# 3_3V_Converter.net
KiCad netlist of a schematic drawn in Altium Designer
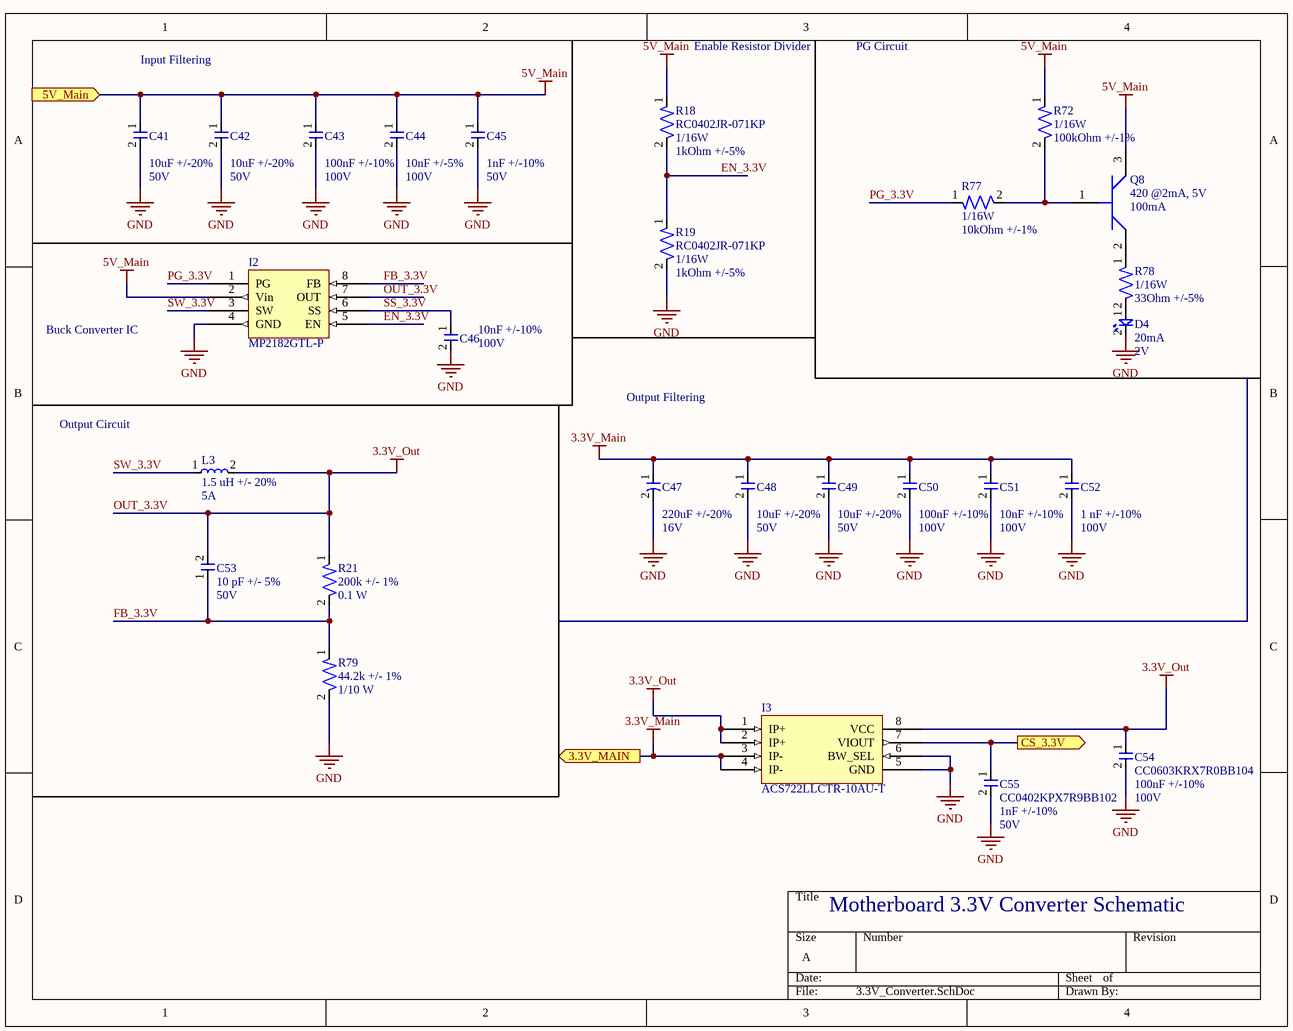
[diagram p0: 3.3V_Converter.SchDoc]

(export (version "E")
  (design (tool "Eeschema 10.0.6"))
  (components
    (comp (ref "C41")
      (value "CL31B106KBHNNNE")
      (footprint "CAP-1206")
      (description "10 µF ±10% 50V Ceramic Capacitor X7R 1206 (3216 Metric)")
      (fields
        (field (name "MANUFACTURER") "Samsung Electro-Mechanics")
        (field (name "CAPACITANCE") "10uF +/-20%")
        (field (name "VOLTAGE RATING") "50V")
      )
      (libsource (lib "MasterLib") (part "CAP-10U-0001"))
    )
    (comp (ref "C42")
      (value "CL31B106KBHNNNE")
      (footprint "CAP-1206")
      (description "10 µF ±10% 50V Ceramic Capacitor X7R 1206 (3216 Metric)")
      (fields
        (field (name "MANUFACTURER") "Samsung Electro-Mechanics")
        (field (name "CAPACITANCE") "10uF +/-20%")
        (field (name "VOLTAGE RATING") "50V")
      )
      (libsource (lib "MasterLib") (part "CAP-10U-0001"))
    )
    (comp (ref "C43")
      (value "CC0603KRX7R0BB104")
      (footprint "CAP-0603")
      (description "CAP CER 0.1UF 100V X7R 0603")
      (fields
        (field (name "MANUFACTURER") "YAGEO")
        (field (name "CAPACITANCE") "100nF +/-10%")
        (field (name "VOLTAGE RATING") "100V")
      )
      (libsource (lib "MasterLib") (part "CAP-100N-0001"))
    )
    (comp (ref "C44")
      (value "C1608C0G2A103J080AC")
      (footprint "CAP-0603")
      (description "CAP CER 10000PF 100V C0G 0603")
      (fields
        (field (name "MANUFACTURER") "TDK Corporation")
        (field (name "CAPACITANCE") "10nF +/-5%")
        (field (name "VOLTAGE RATING") "100V")
      )
      (libsource (lib "MasterLib") (part "CAP-10N-0002"))
    )
    (comp (ref "C45")
      (value "CC0402KPX7R9BB102")
      (footprint "CAP-0402")
      (description "1000 pF ±10% 50V Ceramic Capacitor X7R 0402 (1005 Metric)")
      (fields
        (field (name "MANUFACTURER") "YAGEO")
        (field (name "CAPACITANCE") "1nF +/-10%")
        (field (name "VOLTAGE RATING") "50V")
      )
      (libsource (lib "MasterLib") (part "CAP-1N-0002"))
    )
    (comp (ref "C46")
      (value "CC0402KRX7R0BB103")
      (footprint "CAP-0402")
      (description "10000 pF ±10% 100V Ceramic Capacitor X7R 0402 (1005 Metric)")
      (fields
        (field (name "MANUFACTURER") "YAGEO")
        (field (name "CAPACITANCE") "10nF +/-10%")
        (field (name "VOLTAGE RATING") "100V")
      )
      (libsource (lib "MasterLib") (part "CAP-10N-0001"))
    )
    (comp (ref "C47")
      (value "UUD1C221MCL1GS")
      (footprint "ELEC-220U-0001")
      (description "220 µF 16 V Aluminum Electrolytic Capacitors Radial, Can - SMD 2000 Hrs @ 105°C")
      (fields
        (field (name "MANUFACTURER") "Nichicon")
        (field (name "CAPACITANCE") "220uF +/-20%")
        (field (name "VOLTAGE RATING") "16V")
      )
      (libsource (lib "MasterLib") (part "ELEC-220U-0001"))
    )
    (comp (ref "C48")
      (value "CL31B106KBHNNNE")
      (footprint "CAP-1206")
      (description "10 µF ±10% 50V Ceramic Capacitor X7R 1206 (3216 Metric)")
      (fields
        (field (name "MANUFACTURER") "Samsung Electro-Mechanics")
        (field (name "CAPACITANCE") "10uF +/-20%")
        (field (name "VOLTAGE RATING") "50V")
      )
      (libsource (lib "MasterLib") (part "CAP-10U-0001"))
    )
    (comp (ref "C49")
      (value "CL31B106KBHNNNE")
      (footprint "CAP-1206")
      (description "10 µF ±10% 50V Ceramic Capacitor X7R 1206 (3216 Metric)")
      (fields
        (field (name "MANUFACTURER") "Samsung Electro-Mechanics")
        (field (name "CAPACITANCE") "10uF +/-20%")
        (field (name "VOLTAGE RATING") "50V")
      )
      (libsource (lib "MasterLib") (part "CAP-10U-0001"))
    )
    (comp (ref "C50")
      (value "CC0603KRX7R0BB104")
      (footprint "CAP-0603")
      (description "CAP CER 0.1UF 100V X7R 0603")
      (fields
        (field (name "MANUFACTURER") "YAGEO")
        (field (name "CAPACITANCE") "100nF +/-10%")
        (field (name "VOLTAGE RATING") "100V")
      )
      (libsource (lib "MasterLib") (part "CAP-100N-0001"))
    )
    (comp (ref "C51")
      (value "CC0402KRX7R0BB103")
      (footprint "CAP-0402")
      (description "10000 pF ±10% 100V Ceramic Capacitor X7R 0402 (1005 Metric)")
      (fields
        (field (name "MANUFACTURER") "YAGEO")
        (field (name "CAPACITANCE") "10nF +/-10%")
        (field (name "VOLTAGE RATING") "100V")
      )
      (libsource (lib "MasterLib") (part "CAP-10N-0001"))
    )
    (comp (ref "C52")
      (value "CAP-1N-0001")
      (footprint "CAP-0603")
      (description "1000 pF ±10% 100V Ceramic Capacitor X7R 0603 (1608 Metric)")
      (fields (field (name "CAPACITANCE") "1 nF +/-10%") (field (name "VOLTAGE") "100V"))
      (libsource (lib "MasterLib") (part "CAP-1N-0001"))
    )
    (comp (ref "C53")
      (value "0603N100J500CT")
      (footprint "CAP-0603")
      (description "10 pF ±5% 50V Ceramic Capacitor C0G, NP0 0603 (1608 Metric)")
      (fields
        (field (name "MANUFACTURER") "Walshin Technology Corporation")
        (field (name "CAPACITANCE") "10 pF +/- 5%")
        (field (name "VOLTAGE RATING") "50V")
      )
      (libsource (lib "MasterLib") (part "CAP-10P-0001"))
    )
    (comp (ref "C54")
      (value "CC0603KRX7R0BB104")
      (footprint "CAP-0603")
      (description "CAP CER 0.1UF 100V X7R 0603")
      (fields
        (field (name "MANUFACTURER") "YAGEO")
        (field (name "CAPACITANCE") "100nF +/-10%")
        (field (name "VOLTAGE RATING") "100V")
      )
      (libsource (lib "MasterLib") (part "CAP-100N-0001"))
    )
    (comp (ref "C55")
      (value "CC0402KPX7R9BB102")
      (footprint "CAP-0402")
      (description "1000 pF ±10% 50V Ceramic Capacitor X7R 0402 (1005 Metric)")
      (fields
        (field (name "MANUFACTURER") "YAGEO")
        (field (name "CAPACITANCE") "1nF +/-10%")
        (field (name "VOLTAGE RATING") "50V")
      )
      (libsource (lib "MasterLib") (part "CAP-1N-0002"))
    )
    (comp (ref "D4")
      (value "150060AS75000")
      (footprint "LED-0603")
      (description "CAP CER 0.1UF 100V X7R 0603")
      (fields
        (field (name "MANUFACTURER") "Wurth Electronik")
        (field (name "CURRENT RATING") "20mA")
        (field (name "VF") "2V")
      )
      (libsource (lib "MasterLib") (part "LED_Amber_0001"))
    )
    (comp (ref "I2")
      (value "MP2182GTL-P")
      (footprint "IC-SOT583")
      (description "Buck Switching Regulator IC Positive Adjustable 0.6V 1 Output 2A SOT-583")
      (fields (field (name "MANUFACTURER") "Monolithic Power Systems"))
      (libsource (lib "MasterLib") (part "IC-BUCK-0003"))
    )
    (comp (ref "I3")
      (value "ACS722LLCTR-10AU-T")
      (footprint "IC-CURRENT-0001")
      (description "Current Sensor 10A 1 Channel Hall Effect, Open Loop Unidirectional 8-SOIC (0.154\", 3.90mm Width)")
      (libsource (lib "MasterLib") (part "IC-CURRENT-0001"))
    )
    (comp (ref "L3")
      (value "SRP3212-1R5M")
      (footprint "IND-1210")
      (description "1.5 µH Shielded Drum Core, Wirewound Inductor 4.4 A 53mOhm Max 1210 (3225 Metric)")
      (fields
        (field (name "MANUFACTURER") "Bourns Inc.")
        (field (name "INDUCTANCE") "1.5 uH +/- 20%")
        (field (name "SATURATION CURRENT") "5A")
      )
      (libsource (lib "MasterLib") (part "PWRIND-1.5U-0001"))
    )
    (comp (ref "Q8")
      (value "BC847C,235")
      (footprint "NPN-420-0001")
      (description "Bipolar (BJT) Transistor NPN 45 V 100 mA 100MHz 250 mW Surface Mount TO-236AB")
      (fields (field (name "HFE") "420 @2mA, 5V") (field (name "IC") "100mA"))
      (libsource (lib "MasterLib") (part "BJT-420-0001"))
    )
    (comp (ref "R18")
      (value "RC0402JR-071KP")
      (footprint "RES-0402")
      (description "RES SMD 1K OHM 5% 1/16W 0402")
      (fields
        (field (name "MANUFACTURER") "YAGEO")
        (field (name "POWER RATING") "1/16W")
        (field (name "RESISTANCE") "1kOhm +/-5%")
      )
      (libsource (lib "MasterLib") (part "RES-1K-0001"))
    )
    (comp (ref "R19")
      (value "RC0402JR-071KP")
      (footprint "RES-0402")
      (description "RES SMD 1K OHM 5% 1/16W 0402")
      (fields
        (field (name "MANUFACTURER") "YAGEO")
        (field (name "POWER RATING") "1/16W")
        (field (name "RESISTANCE") "1kOhm +/-5%")
      )
      (libsource (lib "MasterLib") (part "RES-1K-0001"))
    )
    (comp (ref "R21")
      (value "ERJ-3EKF2003V")
      (footprint "RES-0603")
      (description "200 kOhms ±1% 0.1W, 1/10W Chip Resistor 0603 (1608 Metric) Automotive AEC-Q200 Thick Film")
      (fields
        (field (name "MANUFACTURER") "Panasonic Electronic Components")
        (field (name "RESISTANCE") "200k +/- 1%")
        (field (name "POWER RATING") "0.1 W")
      )
      (libsource (lib "MasterLib") (part "RES-200K-0001"))
    )
    (comp (ref "R72")
      (value "AF0402FR-07100KL")
      (footprint "RES-0402")
      (fields
        (field (name "MANUFACTURER") "YAGEO")
        (field (name "POWER RATING") "1/16W")
        (field (name "RESISTANCE") "100kOhm +/-1%")
      )
      (libsource (lib "MasterLib") (part "RES-100K-0001"))
    )
    (comp (ref "R77")
      (value "RC0402FR-0710KL")
      (footprint "RES-0402")
      (description "RES 10K OHM 1% 1/16W 0402")
      (fields
        (field (name "MANUFACTURER") "YAGEO")
        (field (name "POWER RATING") "1/16W")
        (field (name "RESISTANCE") "10kOhm +/-1%")
      )
      (libsource (lib "MasterLib") (part "RES-10K-0001"))
    )
    (comp (ref "R78")
      (value "RC0402JR-0733RP")
      (footprint "RES-0402")
      (description "RES SMD 33 OHM 5% 1/16W 0402")
      (fields
        (field (name "MANUFACTURER") "YAGEO")
        (field (name "POWER RATING") "1/16W")
        (field (name "RESISTANCE") "33Ohm +/-5%")
      )
      (libsource (lib "MasterLib") (part "RES-33-0001"))
    )
    (comp (ref "R79")
      (value "RMCF0603FT44K2")
      (footprint "RES-0603")
      (description "44.2 kOhms ±1% 0.1W, 1/10W Chip Resistor 0603 (1608 Metric) Automotive AEC-Q200 Thick Film")
      (fields (field (name "RESISTANCE") "44.2k +/- 1%") (field (name "POWER") "1/10 W"))
      (libsource (lib "MasterLib") (part "RES-44.2K-0001"))
    )
  )
  (nets
    (net (code "1") (name "/CS_3.3V") (class "Default")
      (node (ref "C55") (pin "1") (pinfunction "1_1") (pintype "passive"))
      (node (ref "I3") (pin "7") (pinfunction "VIOUT_7") (pintype "output"))
    )
    (net (code "2") (name "/EN_3.3V") (class "Default")
      (node (ref "I2") (pin "5") (pinfunction "EN_5") (pintype "input"))
      (node (ref "R18") (pin "2") (pinfunction "2_2") (pintype "passive"))
      (node (ref "R19") (pin "1") (pinfunction "1_1") (pintype "passive"))
    )
    (net (code "3") (name "/FB_3.3V") (class "Default")
      (node (ref "C53") (pin "1") (pinfunction "1_1") (pintype "passive"))
      (node (ref "I2") (pin "8") (pinfunction "FB_8") (pintype "input"))
      (node (ref "R21") (pin "2") (pinfunction "2_2") (pintype "passive"))
      (node (ref "R79") (pin "1") (pinfunction "1_1") (pintype "passive"))
    )
    (net (code "4") (name "/PG_3.3V") (class "Default")
      (node (ref "I2") (pin "1") (pinfunction "PG_1") (pintype "power_in"))
      (node (ref "R77") (pin "1") (pinfunction "1_1") (pintype "passive"))
    )
    (net (code "5") (name "/SS_3.3V") (class "Default")
      (node (ref "C46") (pin "1") (pinfunction "1_1") (pintype "passive"))
      (node (ref "I2") (pin "6") (pinfunction "SS_6") (pintype "input"))
    )
    (net (code "6") (name "/SW_3.3V") (class "Default")
      (node (ref "I2") (pin "3") (pinfunction "SW_3") (pintype "power_in"))
      (node (ref "L3") (pin "1") (pinfunction "1_1") (pintype "passive"))
    )
    (net (code "7") (name "3.3V_Main") (class "Default")
      (node (ref "C47") (pin "1") (pinfunction "1_1") (pintype "passive"))
      (node (ref "C48") (pin "1") (pinfunction "1_1") (pintype "passive"))
      (node (ref "C49") (pin "1") (pinfunction "1_1") (pintype "passive"))
      (node (ref "C50") (pin "1") (pinfunction "1_1") (pintype "passive"))
      (node (ref "C51") (pin "1") (pinfunction "1_1") (pintype "passive"))
      (node (ref "C52") (pin "1") (pinfunction "1_1") (pintype "passive"))
      (node (ref "I3") (pin "3") (pinfunction "IP-_3") (pintype "input"))
      (node (ref "I3") (pin "4") (pinfunction "IP-_4") (pintype "input"))
    )
    (net (code "8") (name "3.3V_Out") (class "Default")
      (node (ref "C53") (pin "2") (pinfunction "2_2") (pintype "passive"))
      (node (ref "C54") (pin "1") (pinfunction "1_1") (pintype "passive"))
      (node (ref "I2") (pin "7") (pinfunction "OUT_7") (pintype "input"))
      (node (ref "I3") (pin "1") (pinfunction "IP+_1") (pintype "input"))
      (node (ref "I3") (pin "2") (pinfunction "IP+_2") (pintype "input"))
      (node (ref "I3") (pin "8") (pinfunction "VCC_8") (pintype "power_in"))
      (node (ref "L3") (pin "2") (pinfunction "2_2") (pintype "passive"))
      (node (ref "R21") (pin "1") (pinfunction "1_1") (pintype "passive"))
    )
    (net (code "9") (name "5V_Main") (class "Default")
      (node (ref "C41") (pin "1") (pinfunction "1_1") (pintype "passive"))
      (node (ref "C42") (pin "1") (pinfunction "1_1") (pintype "passive"))
      (node (ref "C43") (pin "1") (pinfunction "1_1") (pintype "passive"))
      (node (ref "C44") (pin "1") (pinfunction "1_1") (pintype "passive"))
      (node (ref "C45") (pin "1") (pinfunction "1_1") (pintype "passive"))
      (node (ref "I2") (pin "2") (pinfunction "Vin_2") (pintype "output"))
      (node (ref "Q8") (pin "3") (pintype "passive"))
      (node (ref "R18") (pin "1") (pinfunction "1_1") (pintype "passive"))
      (node (ref "R72") (pin "1") (pinfunction "1_1") (pintype "passive"))
    )
    (net (code "10") (name "GND") (class "Default")
      (node (ref "C41") (pin "2") (pinfunction "2_2") (pintype "passive"))
      (node (ref "C42") (pin "2") (pinfunction "2_2") (pintype "passive"))
      (node (ref "C43") (pin "2") (pinfunction "2_2") (pintype "passive"))
      (node (ref "C44") (pin "2") (pinfunction "2_2") (pintype "passive"))
      (node (ref "C45") (pin "2") (pinfunction "2_2") (pintype "passive"))
      (node (ref "C46") (pin "2") (pinfunction "2_2") (pintype "passive"))
      (node (ref "C47") (pin "2") (pinfunction "2_2") (pintype "passive"))
      (node (ref "C48") (pin "2") (pinfunction "2_2") (pintype "passive"))
      (node (ref "C49") (pin "2") (pinfunction "2_2") (pintype "passive"))
      (node (ref "C50") (pin "2") (pinfunction "2_2") (pintype "passive"))
      (node (ref "C51") (pin "2") (pinfunction "2_2") (pintype "passive"))
      (node (ref "C52") (pin "2") (pinfunction "2_2") (pintype "passive"))
      (node (ref "C54") (pin "2") (pinfunction "2_2") (pintype "passive"))
      (node (ref "C55") (pin "2") (pinfunction "2_2") (pintype "passive"))
      (node (ref "D4") (pin "2") (pinfunction "2_2") (pintype "passive"))
      (node (ref "I2") (pin "4") (pinfunction "GND_4") (pintype "output"))
      (node (ref "I3") (pin "5") (pinfunction "GND_5") (pintype "power_in"))
      (node (ref "I3") (pin "6") (pinfunction "BW_SEL_6") (pintype "input"))
      (node (ref "R19") (pin "2") (pinfunction "2_2") (pintype "passive"))
      (node (ref "R79") (pin "2") (pinfunction "2_2") (pintype "passive"))
    )
    (net (code "11") (name "Net-(D4-Pad1)") (class "Default")
      (node (ref "D4") (pin "1") (pinfunction "1_1") (pintype "passive"))
      (node (ref "R78") (pin "2") (pinfunction "2_2") (pintype "passive"))
    )
    (net (code "12") (name "Net-(Q8-Pad1)") (class "Default")
      (node (ref "Q8") (pin "1") (pinfunction "1_1") (pintype "passive"))
      (node (ref "R72") (pin "2") (pinfunction "2_2") (pintype "passive"))
      (node (ref "R77") (pin "2") (pinfunction "2_2") (pintype "passive"))
    )
    (net (code "13") (name "Net-(Q8-Pad2)") (class "Default")
      (node (ref "Q8") (pin "2") (pinfunction "2_2") (pintype "passive"))
      (node (ref "R78") (pin "1") (pinfunction "1_1") (pintype "passive"))
    )
  )
)
